# UsbCanInterface.net
KiCad netlist of a schematic drawn in Altium Designer
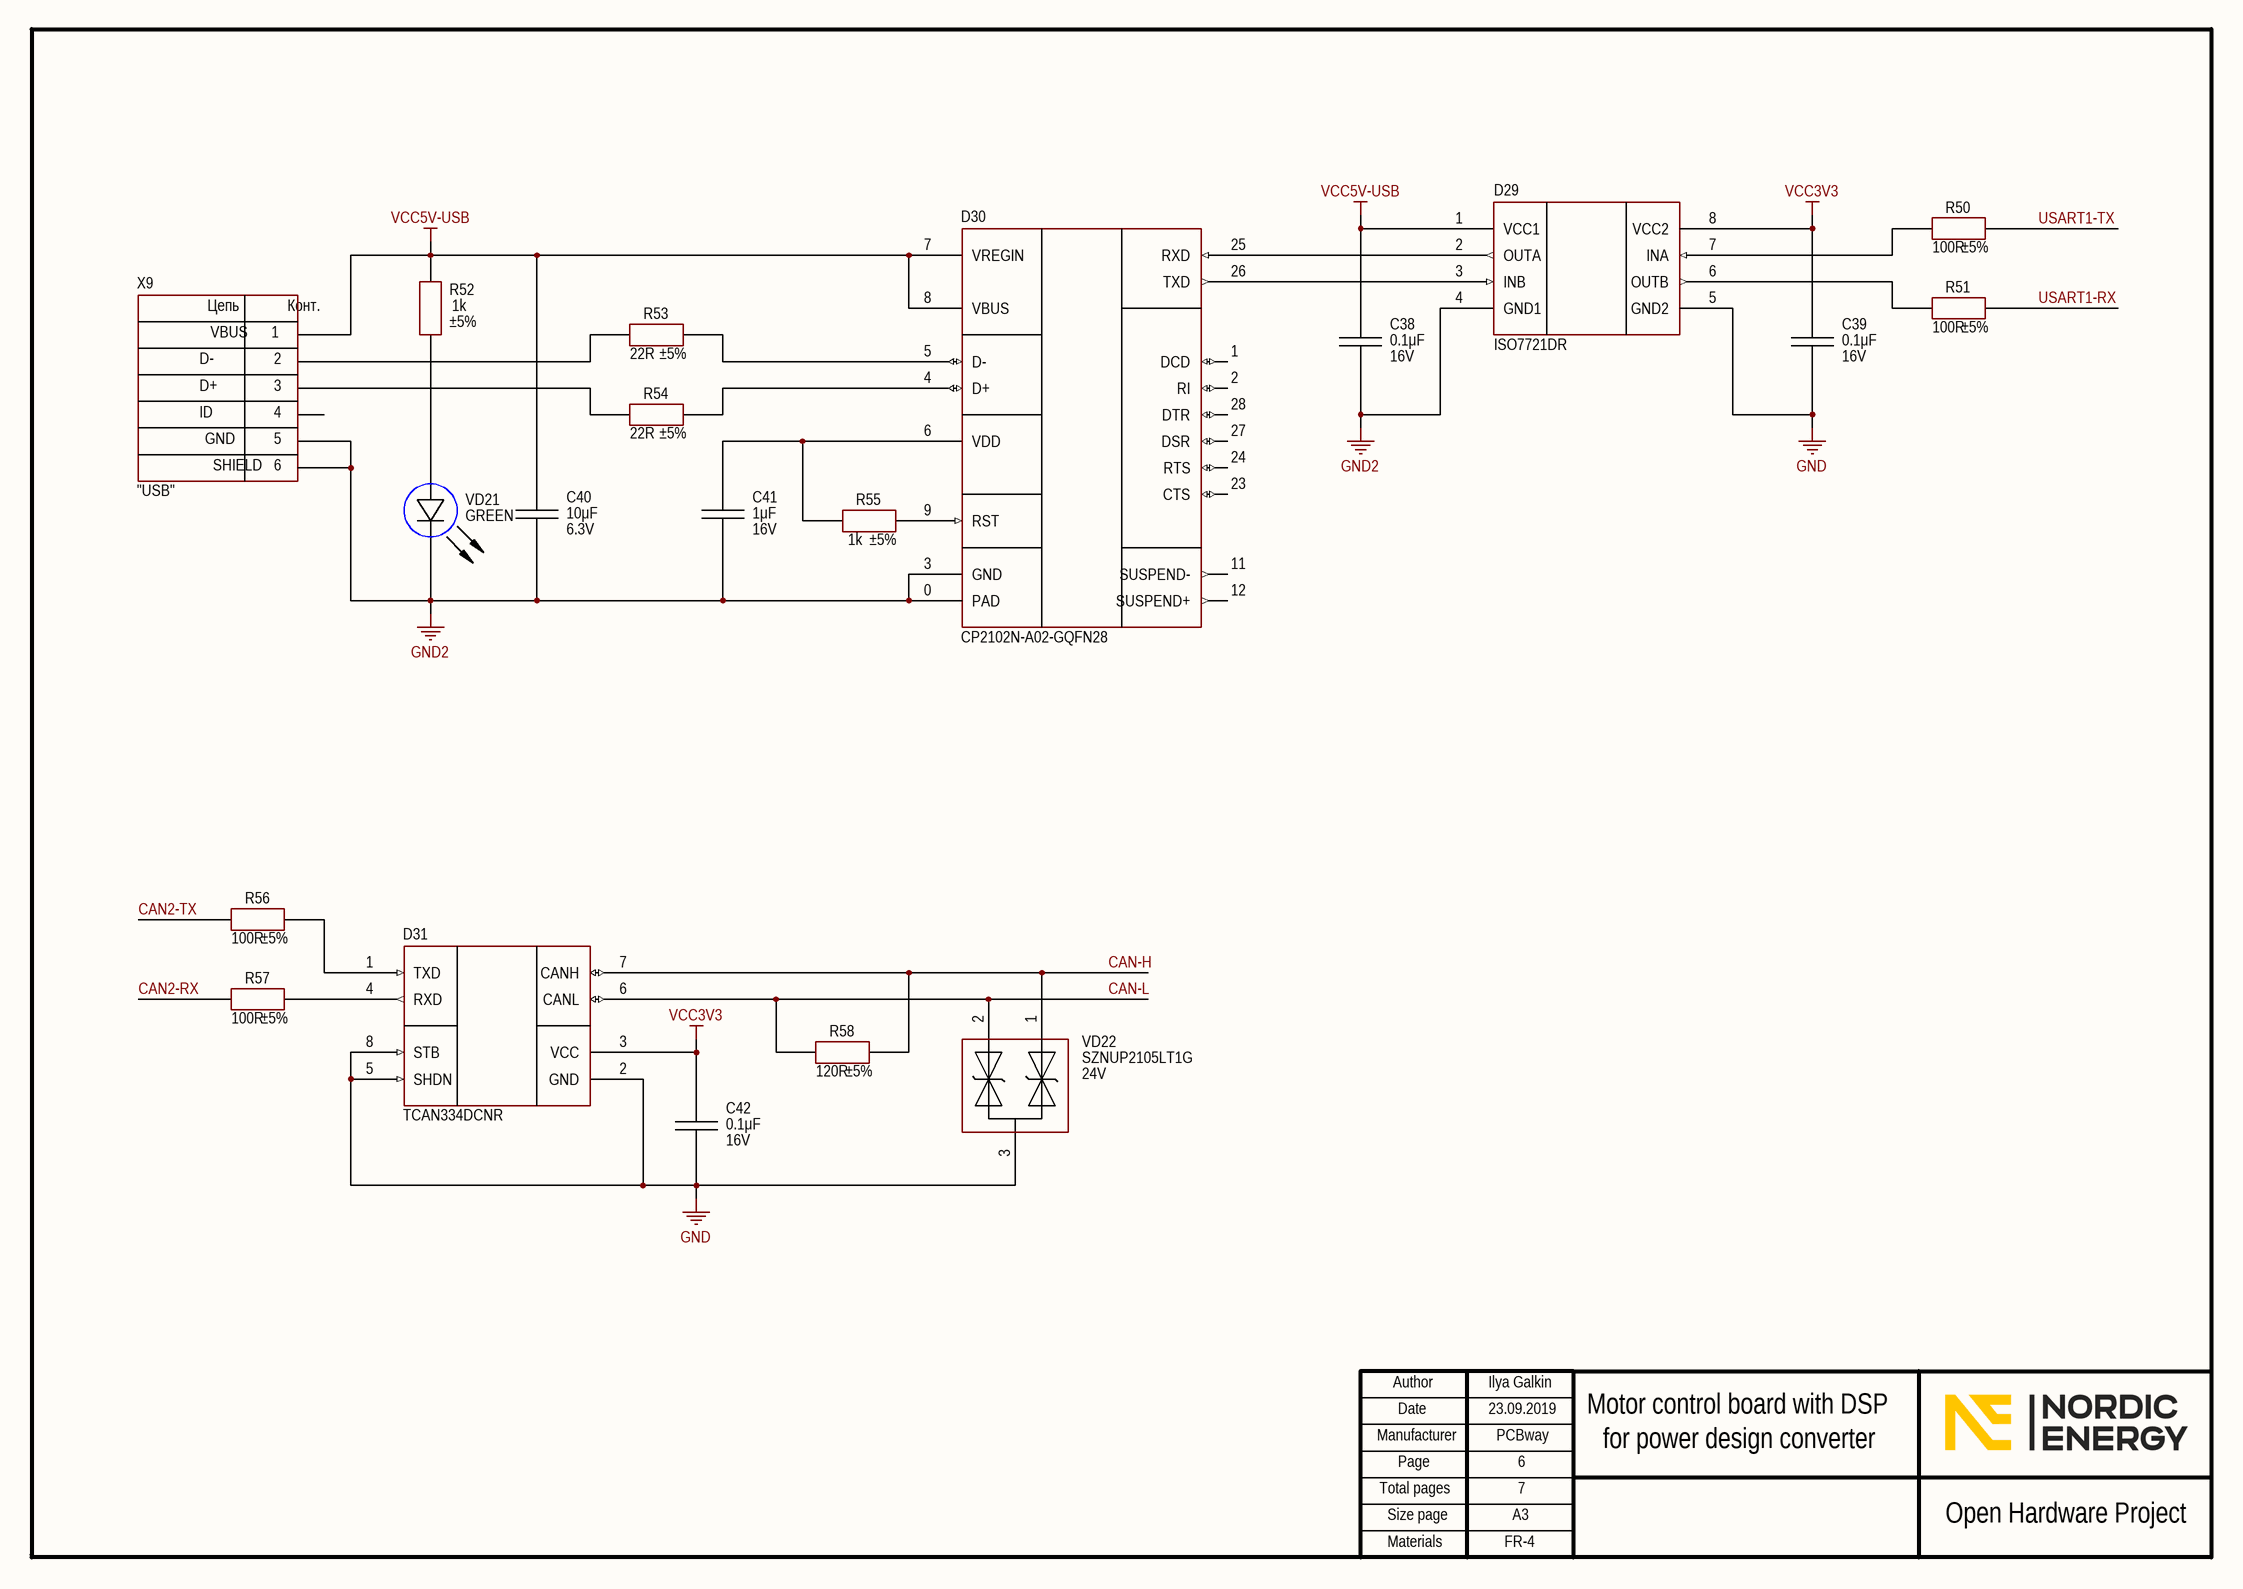
[diagram p0: UsbCanInterface.SchDoc]

(export (version "E")
  (design (tool "Eeschema 10.0.6"))
  (components
    (comp (ref "C38")
      (value "0.1μF")
      (footprint "CAP: 0805")
      (fields
        (field (name "MANUFACTURER") "Yageo")
        (field (name "PARTNUMBER") "CC0805KRX7R7BB104")
        (field (name "VALUEMANUFACTURERPARTNUMBER") "Ceramic capacitor, 0.1μF, X7R, ±10%, 16V, 0805, -55...+125°C")
        (field (name "VOLTAGE") "16V")
      )
      (libsource (lib "Capacitor") (part "Ceramic_0805"))
    )
    (comp (ref "C39")
      (value "0.1μF")
      (footprint "CAP: 0805")
      (fields
        (field (name "MANUFACTURER") "Yageo")
        (field (name "PARTNUMBER") "CC0805KRX7R7BB104")
        (field (name "VALUEMANUFACTURERPARTNUMBER") "Ceramic capacitor, 0.1μF, X7R, ±10%, 16V, 0805, -55...+125°C")
        (field (name "VOLTAGE") "16V")
      )
      (libsource (lib "Capacitor") (part "Ceramic_0805"))
    )
    (comp (ref "C40")
      (value "10μF")
      (footprint "CAP: 0805")
      (fields
        (field (name "MANUFACTURER") "Samsung")
        (field (name "PARTNUMBER") "CL21B106KQQNNNE")
        (field (name "VALUEMANUFACTURERPARTNUMBER") "Ceramic capacitor, 10μF, X7R, ±10%, 6.3V, 0805, -55...+125°C")
        (field (name "VOLTAGE") "6.3V")
      )
      (libsource (lib "Capacitor") (part "Ceramic_0805"))
    )
    (comp (ref "C41")
      (value "1μF")
      (footprint "CAP: 0805")
      (fields
        (field (name "MANUFACTURER") "Yageo")
        (field (name "PARTNUMBER") "CC0805KKX7R7BB105")
        (field (name "VALUEMANUFACTURERPARTNUMBER") "Ceramic capacitor, 1μF, X7R, ±10%, 16V, 0805, -55...+125°C")
        (field (name "VOLTAGE") "16V")
      )
      (libsource (lib "Capacitor") (part "Ceramic_0805"))
    )
    (comp (ref "C42")
      (value "0.1μF")
      (footprint "CAP: 0805")
      (fields
        (field (name "MANUFACTURER") "Yageo")
        (field (name "PARTNUMBER") "CC0805KRX7R7BB104")
        (field (name "VALUEMANUFACTURERPARTNUMBER") "Ceramic capacitor, 0.1μF, X7R, ±10%, 16V, 0805, -55...+125°C")
        (field (name "VOLTAGE") "16V")
      )
      (libsource (lib "Capacitor") (part "Ceramic_0805"))
    )
    (comp (ref "D29")
      (value "~")
      (footprint "8-SOIC")
      (description "Digital isolator")
      (fields
        (field (name "MANUFACTURER") "Texas Instruments")
        (field (name "VALUEMANUFACTURERPARTNUMBER") "IC digital isolator, 100Mbps, 3000Vrms, 2.25...5.5V, -55...+125°C, 8-SOIC")
        (field (name "PARTNUMBER") "ISO7721DR")
      )
      (libsource (lib "IC. Interface") (part "ISO7721DR"))
    )
    (comp (ref "D30")
      (value "~")
      (footprint "28-QFN (5x5)")
      (description "USB-to-UART")
      (fields
        (field (name "MANUFACTURER") "Silicon Labs")
        (field (name "VALUEMANUFACTURERPARTNUMBER") "IC usb-to-uart bridge, USB2.0, 3...3.6V, -40...+85°C, 28-VFQFN")
        (field (name "PARTNUMBER") "CP2102N-A02-GQFN28")
      )
      (libsource (lib "IC. Interface") (part "CP2102N"))
    )
    (comp (ref "D31")
      (value "~")
      (footprint "SOT23-8")
      (description "CAN")
      (fields
        (field (name "MANUFACTURER") "Texas Instruments")
        (field (name "VALUEMANUFACTURERPARTNUMBER") "IC CAN transceiver, 1Mbps, Half-duplex, 3...3.6V, -40...+125°C, SOT23-8")
        (field (name "PARTNUMBER") "TCAN334DCNR")
      )
      (libsource (lib "IC. Interface") (part "TCAN334DCNR"))
    )
    (comp (ref "R50")
      (value "100R")
      (footprint "RES: 0805")
      (fields
        (field (name "MANUFACTURER") "Yageo")
        (field (name "PARTNUMBER") "RC0805JR-07100RL")
        (field (name "VALUEMANUFACTURERPARTNUMBER") "Resistor film, 100R, ±5%, 0805, 0.125W, -55...+125°C")
        (field (name "TOLERANCE") "±5%")
      )
      (libsource (lib "Resistor") (part "Resistor_0805"))
    )
    (comp (ref "R51")
      (value "100R")
      (footprint "RES: 0805")
      (fields
        (field (name "MANUFACTURER") "Yageo")
        (field (name "PARTNUMBER") "RC0805JR-07100RL")
        (field (name "VALUEMANUFACTURERPARTNUMBER") "Resistor film, 100R, ±5%, 0805, 0.125W, -55...+125°C")
        (field (name "TOLERANCE") "±5%")
      )
      (libsource (lib "Resistor") (part "Resistor_0805"))
    )
    (comp (ref "R52")
      (value "1k")
      (footprint "RES: 0805")
      (fields
        (field (name "MANUFACTURER") "Yageo")
        (field (name "PARTNUMBER") "RC0805JR-071KL")
        (field (name "VALUEMANUFACTURERPARTNUMBER") "Resistor film, 1k, ±5%, 0805, 0.125W, -55...+125°C")
        (field (name "TOLERANCE") "±5%")
      )
      (libsource (lib "") (part "Resistor_0805_1"))
    )
    (comp (ref "R53")
      (value "22R")
      (footprint "RES: 0805")
      (fields
        (field (name "MANUFACTURER") "Yageo")
        (field (name "PARTNUMBER") "RC0805JR-0722RL")
        (field (name "VALUEMANUFACTURERPARTNUMBER") "Resistor film, 22R, ±5%, 0805, 0.125W, -55...+125°C")
        (field (name "TOLERANCE") "±5%")
      )
      (libsource (lib "Resistor") (part "Resistor_0805"))
    )
    (comp (ref "R54")
      (value "22R")
      (footprint "RES: 0805")
      (fields
        (field (name "MANUFACTURER") "Yageo")
        (field (name "PARTNUMBER") "RC0805JR-0722RL")
        (field (name "VALUEMANUFACTURERPARTNUMBER") "Resistor film, 22R, ±5%, 0805, 0.125W, -55...+125°C")
        (field (name "TOLERANCE") "±5%")
      )
      (libsource (lib "Resistor") (part "Resistor_0805"))
    )
    (comp (ref "R55")
      (value "1k")
      (footprint "RES: 0805")
      (fields
        (field (name "MANUFACTURER") "Yageo")
        (field (name "PARTNUMBER") "RC0805JR-071KL")
        (field (name "VALUEMANUFACTURERPARTNUMBER") "Resistor film, 1k, ±5%, 0805, 0.125W, -55...+125°C")
        (field (name "TOLERANCE") "±5%")
      )
      (libsource (lib "") (part "Resistor_0805_2"))
    )
    (comp (ref "R56")
      (value "100R")
      (footprint "RES: 0805")
      (fields
        (field (name "MANUFACTURER") "Yageo")
        (field (name "PARTNUMBER") "RC0805JR-07100RL")
        (field (name "VALUEMANUFACTURERPARTNUMBER") "Resistor film, 100R, ±5%, 0805, 0.125W, -55...+125°C")
        (field (name "TOLERANCE") "±5%")
      )
      (libsource (lib "Resistor") (part "Resistor_0805"))
    )
    (comp (ref "R57")
      (value "100R")
      (footprint "RES: 0805")
      (fields
        (field (name "MANUFACTURER") "Yageo")
        (field (name "PARTNUMBER") "RC0805JR-07100RL")
        (field (name "VALUEMANUFACTURERPARTNUMBER") "Resistor film, 100R, ±5%, 0805, 0.125W, -55...+125°C")
        (field (name "TOLERANCE") "±5%")
      )
      (libsource (lib "Resistor") (part "Resistor_0805"))
    )
    (comp (ref "R58")
      (value "120R")
      (footprint "RES: 0805")
      (fields
        (field (name "MANUFACTURER") "Yageo")
        (field (name "PARTNUMBER") "RC0805JR-07120RL")
        (field (name "VALUEMANUFACTURERPARTNUMBER") "Resistor film, 120R, ±5%, 0805, 0.125W, -55...+125°C")
        (field (name "TOLERANCE") "±5%")
      )
      (libsource (lib "Resistor") (part "Resistor_0805"))
    )
    (comp (ref "VD21")
      (value "~")
      (footprint "LED: 0805G")
      (fields
        (field (name "MANUFACTURER") "Wurth")
        (field (name "VALUEMANUFACTURERPARTNUMBER") "LED, 20mA, 2V, 0805, -55...+150°C")
        (field (name "PARTNUMBER") "150080VS75000")
        (field (name "COLOR") "GREEN")
      )
      (libsource (lib "Diode") (part "LED_single"))
    )
    (comp (ref "VD22")
      (value "~")
      (footprint "SOT23")
      (fields
        (field (name "MANUFACTURER") "ON Semiconductor")
        (field (name "VALUEMANUFACTURERPARTNUMBER") "Zener diode, 24V, 350W peak, 30pF, 17Ohm, SOT-23, -55...+150°C")
        (field (name "VOLTAGE") "24V")
        (field (name "PARTNUMBER") "SZNUP2105LT1G")
      )
      (libsource (lib "Diode") (part "TVS_array"))
    )
    (comp (ref "X9")
      (value "~")
      (footprint "CON: USB micro-A (ZX62-B-5PA)")
      (fields
        (field (name "MANUFACTURER") "Hirose Electric")
        (field (name "VALUEMANUFACTURERPARTNUMBER") "USB micro B")
        (field (name "PARTNUMBER") "ZX62-B-5PA")
        (field (name "COMMENTTEXT") "\"USB\"")
      )
      (libsource (lib "Connector") (part "Connector_USB_micro_B"))
    )
  )
  (nets
    (net (code "1") (name "/CAN-H") (class "Default")
      (node (ref "D31") (pin "7") (pinfunction "CANH_7") (pintype "bidirectional"))
      (node (ref "R58") (pin "2") (pinfunction "2_2") (pintype "passive"))
      (node (ref "VD22") (pin "1") (pintype "passive"))
    )
    (net (code "2") (name "/CAN-L") (class "Default")
      (node (ref "D31") (pin "6") (pinfunction "CANL_6") (pintype "bidirectional"))
      (node (ref "R58") (pin "1") (pinfunction "1_1") (pintype "passive"))
      (node (ref "VD22") (pin "2") (pintype "passive"))
    )
    (net (code "3") (name "/CAN2-RX") (class "Default")
      (node (ref "R57") (pin "1") (pinfunction "1_1") (pintype "passive"))
    )
    (net (code "4") (name "/CAN2-TX") (class "Default")
      (node (ref "R56") (pin "1") (pinfunction "1_1") (pintype "passive"))
    )
    (net (code "5") (name "/USART1-RX") (class "Default")
      (node (ref "R51") (pin "2") (pinfunction "2_2") (pintype "passive"))
    )
    (net (code "6") (name "/USART1-TX") (class "Default")
      (node (ref "R50") (pin "2") (pinfunction "2_2") (pintype "passive"))
    )
    (net (code "7") (name "GND") (class "Default")
      (node (ref "C39") (pin "1") (pinfunction "1_1") (pintype "power_in"))
      (node (ref "C42") (pin "1") (pinfunction "1_1") (pintype "power_in"))
      (node (ref "D29") (pin "5") (pinfunction "GND2_5") (pintype "passive"))
      (node (ref "D31") (pin "2") (pinfunction "GND_2") (pintype "passive"))
      (node (ref "D31") (pin "5") (pinfunction "SHDN_5") (pintype "input"))
      (node (ref "D31") (pin "8") (pinfunction "STB_8") (pintype "input"))
      (node (ref "VD22") (pin "3") (pintype "passive"))
    )
    (net (code "8") (name "GND2") (class "Default")
      (node (ref "C38") (pin "1") (pinfunction "1_1") (pintype "power_in"))
      (node (ref "C40") (pin "1") (pinfunction "1_1") (pintype "power_in"))
      (node (ref "C41") (pin "1") (pinfunction "1_1") (pintype "power_in"))
      (node (ref "D29") (pin "4") (pinfunction "GND1_4") (pintype "passive"))
      (node (ref "D30") (pin "0") (pinfunction "PAD_0") (pintype "passive"))
      (node (ref "D30") (pin "3") (pinfunction "GND_3") (pintype "passive"))
      (node (ref "VD21") (pin "2") (pinfunction "C_2") (pintype "passive"))
      (node (ref "X9") (pin "0") (pinfunction "0_0") (pintype "passive"))
      (node (ref "X9") (pin "5") (pinfunction "5_5") (pintype "passive"))
    )
    (net (code "9") (name "Net-(D29-INA)") (class "Default")
      (node (ref "D29") (pin "7") (pinfunction "INA_7") (pintype "input"))
      (node (ref "R50") (pin "1") (pinfunction "1_1") (pintype "passive"))
    )
    (net (code "10") (name "Net-(D29-INB)") (class "Default")
      (node (ref "D29") (pin "3") (pinfunction "INB_3") (pintype "input"))
      (node (ref "D30") (pin "26") (pinfunction "TXD_26") (pintype "output"))
    )
    (net (code "11") (name "Net-(D29-OUTA)") (class "Default")
      (node (ref "D29") (pin "2") (pinfunction "OUTA_2") (pintype "output"))
      (node (ref "D30") (pin "25") (pinfunction "RXD_25") (pintype "input"))
    )
    (net (code "12") (name "Net-(D29-OUTB)") (class "Default")
      (node (ref "D29") (pin "6") (pinfunction "OUTB_6") (pintype "output"))
      (node (ref "R51") (pin "1") (pinfunction "1_1") (pintype "passive"))
    )
    (net (code "13") (name "Net-(D30-D+)") (class "Default")
      (node (ref "D30") (pin "4") (pinfunction "D+_4") (pintype "bidirectional"))
      (node (ref "R54") (pin "2") (pinfunction "2_2") (pintype "passive"))
    )
    (net (code "14") (name "Net-(D30-D-)") (class "Default")
      (node (ref "D30") (pin "5") (pinfunction "D-_5") (pintype "bidirectional"))
      (node (ref "R53") (pin "2") (pinfunction "2_2") (pintype "passive"))
    )
    (net (code "15") (name "Net-(D30-RST)") (class "Default")
      (node (ref "D30") (pin "9") (pinfunction "RST_9") (pintype "input"))
      (node (ref "R55") (pin "1") (pinfunction "1_1") (pintype "passive"))
    )
    (net (code "16") (name "Net-(D30-VDD)") (class "Default")
      (node (ref "C41") (pin "2") (pinfunction "2_2") (pintype "power_in"))
      (node (ref "D30") (pin "6") (pinfunction "VDD_6") (pintype "passive"))
      (node (ref "R55") (pin "2") (pinfunction "2_2") (pintype "passive"))
    )
    (net (code "17") (name "Net-(D31-RXD)") (class "Default")
      (node (ref "D31") (pin "4") (pinfunction "RXD_4") (pintype "output"))
      (node (ref "R57") (pin "2") (pinfunction "2_2") (pintype "passive"))
    )
    (net (code "18") (name "Net-(D31-TXD)") (class "Default")
      (node (ref "D31") (pin "1") (pinfunction "TXD_1") (pintype "input"))
      (node (ref "R56") (pin "2") (pinfunction "2_2") (pintype "passive"))
    )
    (net (code "19") (name "Net-(R53-Pad1)") (class "Default")
      (node (ref "R53") (pin "1") (pinfunction "1_1") (pintype "passive"))
      (node (ref "X9") (pin "2") (pinfunction "2_2") (pintype "passive"))
    )
    (net (code "20") (name "Net-(R54-Pad1)") (class "Default")
      (node (ref "R54") (pin "1") (pinfunction "1_1") (pintype "passive"))
      (node (ref "X9") (pin "3") (pinfunction "3_3") (pintype "passive"))
    )
    (net (code "21") (name "Net-(VD21-A)") (class "Default")
      (node (ref "R52") (pin "1") (pinfunction "1_1") (pintype "passive"))
      (node (ref "VD21") (pin "1") (pinfunction "A_1") (pintype "passive"))
    )
    (net (code "22") (name "VCC3V3") (class "Default")
      (node (ref "C39") (pin "2") (pinfunction "2_2") (pintype "power_in"))
      (node (ref "C42") (pin "2") (pinfunction "2_2") (pintype "power_in"))
      (node (ref "D29") (pin "8") (pinfunction "VCC2_8") (pintype "passive"))
      (node (ref "D31") (pin "3") (pinfunction "VCC_3") (pintype "passive"))
    )
    (net (code "23") (name "VCC5V-USB") (class "Default")
      (node (ref "C38") (pin "2") (pinfunction "2_2") (pintype "power_in"))
      (node (ref "C40") (pin "2") (pinfunction "2_2") (pintype "power_in"))
      (node (ref "D29") (pin "1") (pinfunction "VCC1_1") (pintype "passive"))
      (node (ref "D30") (pin "7") (pinfunction "VREGIN_7") (pintype "passive"))
      (node (ref "D30") (pin "8") (pinfunction "VBUS_8") (pintype "passive"))
      (node (ref "R52") (pin "2") (pinfunction "2_2") (pintype "passive"))
      (node (ref "X9") (pin "1") (pintype "passive"))
    )
    (net (code "24") (name "unconnected-(D30-CTS-Pad23)") (class "Default")
      (node (ref "D30") (pin "23") (pinfunction "CTS_23") (pintype "bidirectional"))
    )
    (net (code "25") (name "unconnected-(D30-DCD-Pad1)") (class "Default")
      (node (ref "D30") (pin "1") (pinfunction "DCD_1") (pintype "bidirectional"))
    )
    (net (code "26") (name "unconnected-(D30-DSR-Pad27)") (class "Default")
      (node (ref "D30") (pin "27") (pinfunction "DSR_27") (pintype "bidirectional"))
    )
    (net (code "27") (name "unconnected-(D30-DTR-Pad28)") (class "Default")
      (node (ref "D30") (pin "28") (pinfunction "DTR_28") (pintype "bidirectional"))
    )
    (net (code "28") (name "unconnected-(D30-RI-Pad2)") (class "Default")
      (node (ref "D30") (pin "2") (pinfunction "RI_2") (pintype "bidirectional"))
    )
    (net (code "29") (name "unconnected-(D30-RTS-Pad24)") (class "Default")
      (node (ref "D30") (pin "24") (pinfunction "RTS_24") (pintype "bidirectional"))
    )
    (net (code "30") (name "unconnected-(D30-SUSPEND+-Pad12)") (class "Default")
      (node (ref "D30") (pin "12") (pinfunction "SUSPEND+_12") (pintype "output"))
    )
    (net (code "31") (name "unconnected-(D30-SUSPEND--Pad11)") (class "Default")
      (node (ref "D30") (pin "11") (pinfunction "SUSPEND-_11") (pintype "output"))
    )
    (net (code "32") (name "unconnected-(X9-Pad4)") (class "Default")
      (node (ref "X9") (pin "4") (pinfunction "4_4") (pintype "passive"))
    )
  )
)
